# V2.net
KiCad netlist of a schematic drawn in Altium Designer
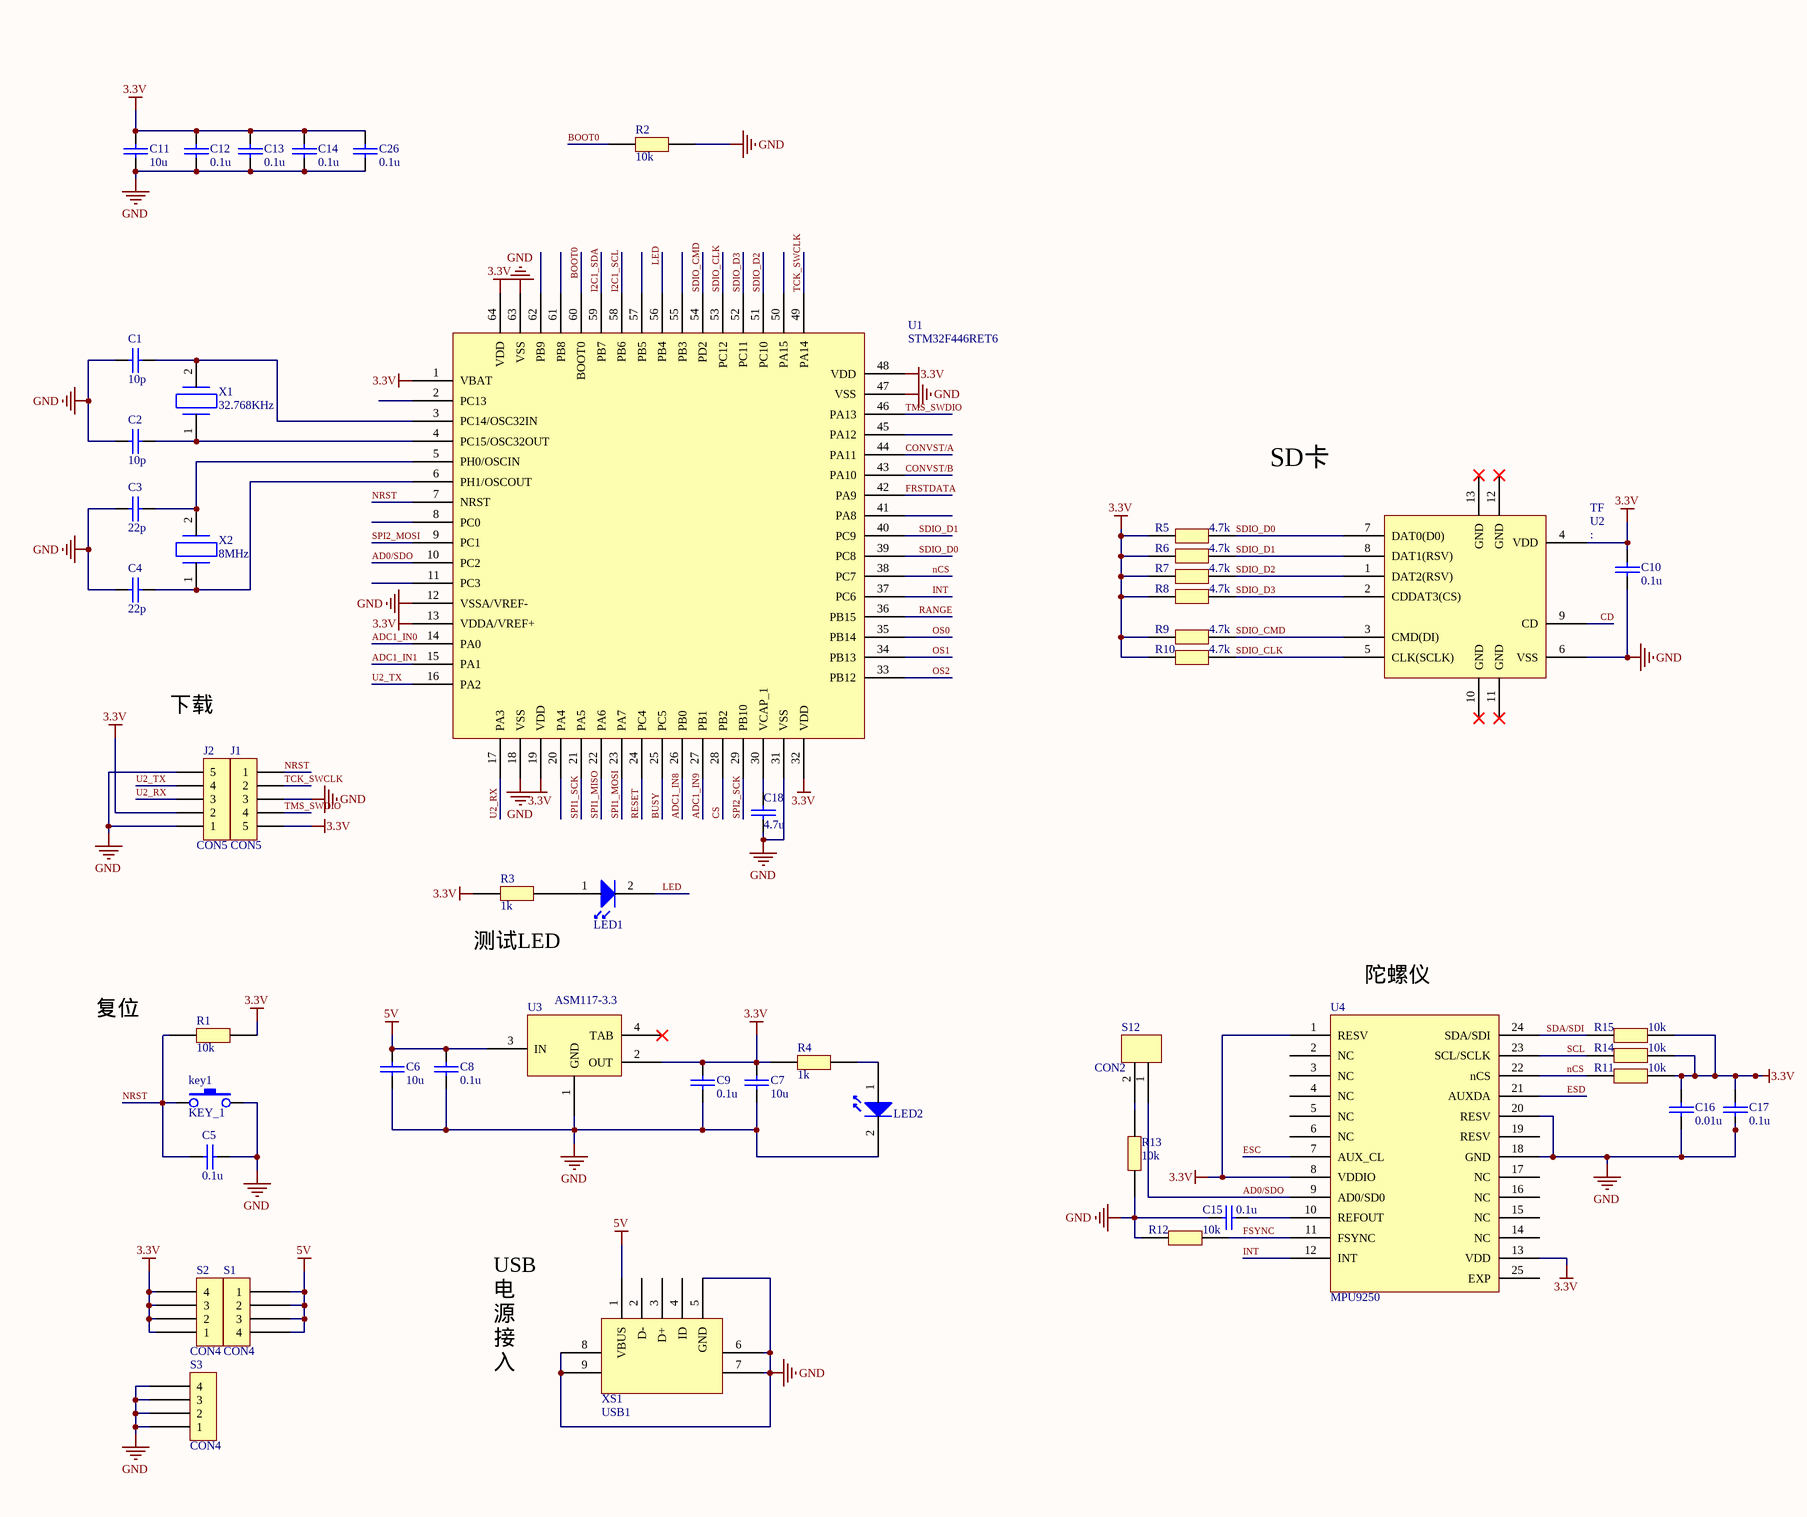
[diagram p0: V2.SchDoc, left]
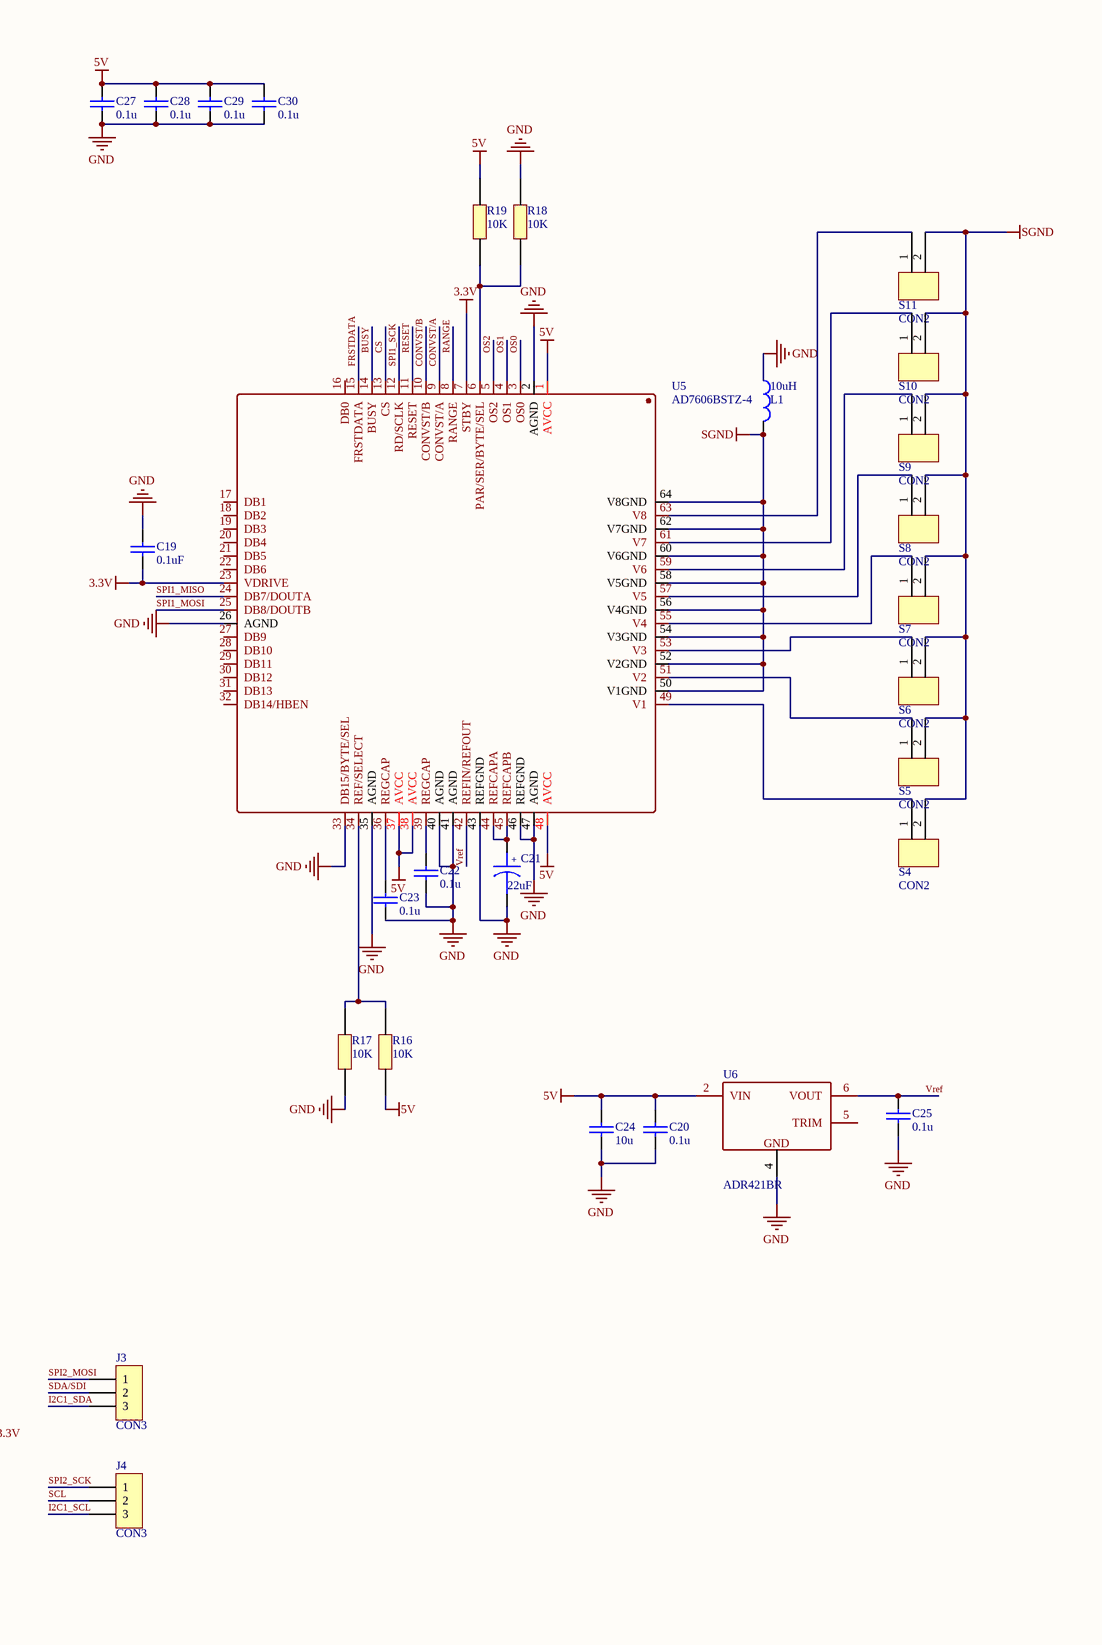
[diagram p1: V2.SchDoc, right]

(export (version "E")
  (design (tool "Eeschema 10.0.6"))
  (components
    (comp (ref "10uH") (value "L1") (footprint "0805") (libsource (lib "元件库") (part "L")))
    (comp (ref "C1") (value "10p") (footprint "0603-cap") (libsource (lib "元件库") (part "CAP")))
    (comp (ref "C2") (value "10p") (footprint "0603-cap") (libsource (lib "元件库") (part "CAP")))
    (comp (ref "C3") (value "22p") (footprint "0603-cap") (libsource (lib "元件库") (part "CAP")))
    (comp (ref "C4") (value "22p") (footprint "0603-cap") (libsource (lib "元件库") (part "CAP")))
    (comp (ref "C5") (value "0.1u") (footprint "0603-cap") (libsource (lib "元件库") (part "CAP")))
    (comp (ref "C6") (value "10u") (footprint "0603-cap") (libsource (lib "元件库") (part "CAP")))
    (comp (ref "C7") (value "10u") (footprint "0603-cap") (libsource (lib "元件库") (part "CAP")))
    (comp (ref "C8") (value "0.1u") (footprint "0603-cap") (libsource (lib "元件库") (part "CAP")))
    (comp (ref "C9") (value "0.1u") (footprint "0603-cap") (libsource (lib "元件库") (part "CAP")))
    (comp (ref "C10") (value "0.1u") (footprint "0603-cap") (libsource (lib "元件库") (part "CAP")))
    (comp (ref "C11") (value "10u") (footprint "0603-cap") (libsource (lib "元件库") (part "CAP")))
    (comp (ref "C12") (value "0.1u") (footprint "0603-cap") (libsource (lib "元件库") (part "CAP")))
    (comp (ref "C13") (value "0.1u") (footprint "0603-cap") (libsource (lib "元件库") (part "CAP")))
    (comp (ref "C14") (value "0.1u") (footprint "0603-cap") (libsource (lib "元件库") (part "CAP")))
    (comp (ref "C15") (value "0.1u") (footprint "0603-cap") (libsource (lib "元件库") (part "CAP")))
    (comp (ref "C16") (value "0.01u") (footprint "0603-cap") (libsource (lib "元件库") (part "CAP")))
    (comp (ref "C17") (value "0.1u") (footprint "0603-cap") (libsource (lib "元件库") (part "CAP")))
    (comp (ref "C18") (value "4.7u") (footprint "0603-cap") (libsource (lib "元件库") (part "CAP")))
    (comp (ref "C19") (value "0.1uF") (footprint "0603-cap") (libsource (lib "元件库") (part "CAP")))
    (comp (ref "C20") (value "0.1u") (footprint "0603-cap") (libsource (lib "元件库") (part "CAP")))
    (comp (ref "C21")
      (value "22uF")
      (footprint "C1206_Y")
      (description "Capacitor")
      (libsource (lib "元件库") (part "电解电容"))
    )
    (comp (ref "C22") (value "0.1u") (footprint "0603-cap") (libsource (lib "元件库") (part "CAP")))
    (comp (ref "C23") (value "0.1u") (footprint "0603-cap") (libsource (lib "元件库") (part "CAP")))
    (comp (ref "C24") (value "10u") (footprint "0603-cap") (libsource (lib "元件库") (part "CAP")))
    (comp (ref "C25") (value "0.1u") (footprint "0603-cap") (libsource (lib "元件库") (part "CAP")))
    (comp (ref "C26") (value "0.1u") (footprint "0603-cap") (libsource (lib "元件库") (part "CAP")))
    (comp (ref "C27") (value "0.1u") (footprint "0603-cap") (libsource (lib "元件库") (part "CAP")))
    (comp (ref "C28") (value "0.1u") (footprint "0603-cap") (libsource (lib "元件库") (part "CAP")))
    (comp (ref "C29") (value "0.1u") (footprint "0603-cap") (libsource (lib "元件库") (part "CAP")))
    (comp (ref "C30") (value "0.1u") (footprint "0603-cap") (libsource (lib "元件库") (part "CAP")))
    (comp (ref "J1") (value "CON5") (footprint "SIP05") (libsource (lib "元件库") (part "CON5")))
    (comp (ref "J2") (value "CON5") (footprint "SIP05") (libsource (lib "") (part "CON5_1")))
    (comp (ref "J3") (value "CON3") (footprint "SIP03") (libsource (lib "元件库") (part "CON3")))
    (comp (ref "J4") (value "CON3") (footprint "SIP03") (libsource (lib "元件库") (part "CON3")))
    (comp (ref "key1") (value "KEY_1") (footprint "key - duplicate5") (libsource (lib "元件库") (part "KEY_1")))
    (comp (ref "LED1") (value "LED?") (footprint "LED") (libsource (lib "元件库") (part "LED")))
    (comp (ref "LED2") (value "LED?") (footprint "LED") (libsource (lib "元件库") (part "LED")))
    (comp (ref "R1") (value "10k") (footprint "0603-res") (libsource (lib "") (part "RES_2")))
    (comp (ref "R2") (value "10k") (footprint "0603-res") (libsource (lib "") (part "RES_2")))
    (comp (ref "R3") (value "1k") (footprint "0603-res") (libsource (lib "") (part "RES_2")))
    (comp (ref "R4") (value "1k") (footprint "0603-res") (libsource (lib "") (part "RES_1")))
    (comp (ref "R5") (value "4.7k") (footprint "0603-res") (libsource (lib "") (part "RES_1")))
    (comp (ref "R6") (value "4.7k") (footprint "0603-res") (libsource (lib "") (part "RES_1")))
    (comp (ref "R7") (value "4.7k") (footprint "0603-res") (libsource (lib "") (part "RES_1")))
    (comp (ref "R8") (value "4.7k") (footprint "0603-res") (libsource (lib "") (part "RES_1")))
    (comp (ref "R9") (value "4.7k") (footprint "0603-res") (libsource (lib "") (part "RES_1")))
    (comp (ref "R10") (value "4.7k") (footprint "0603-res") (libsource (lib "") (part "RES_1")))
    (comp (ref "R11") (value "10k") (footprint "0603-res") (libsource (lib "") (part "RES_1")))
    (comp (ref "R12") (value "10k") (footprint "0603-res") (libsource (lib "") (part "RES_1")))
    (comp (ref "R13") (value "10k") (footprint "0603-res") (libsource (lib "元件库") (part "RES")))
    (comp (ref "R14") (value "10k") (footprint "0603-res") (libsource (lib "") (part "RES_1")))
    (comp (ref "R15") (value "10k") (footprint "0603-res") (libsource (lib "") (part "RES_1")))
    (comp (ref "R16") (value "10K") (footprint "0603-res") (libsource (lib "元件库") (part "RES")))
    (comp (ref "R17") (value "10K") (footprint "0603-res") (libsource (lib "元件库") (part "RES")))
    (comp (ref "R18") (value "10K") (footprint "0603-res") (libsource (lib "元件库") (part "RES")))
    (comp (ref "R19") (value "10K") (footprint "0603-res") (libsource (lib "元件库") (part "RES")))
    (comp (ref "S1") (value "CON4") (footprint "SIP04") (libsource (lib "元件库") (part "CON4")))
    (comp (ref "S2") (value "CON4") (footprint "SIP04") (libsource (lib "") (part "CON4_1")))
    (comp (ref "S3") (value "CON4") (footprint "SIP04") (libsource (lib "") (part "CON4_1")))
    (comp (ref "S4") (value "CON2") (footprint "SIP02") (libsource (lib "") (part "CON2_1")))
    (comp (ref "S5") (value "CON2") (footprint "SIP02") (libsource (lib "") (part "CON2_1")))
    (comp (ref "S6") (value "CON2") (footprint "SIP02") (libsource (lib "") (part "CON2_1")))
    (comp (ref "S7") (value "CON2") (footprint "SIP02") (libsource (lib "") (part "CON2_1")))
    (comp (ref "S8") (value "CON2") (footprint "SIP02") (libsource (lib "") (part "CON2_1")))
    (comp (ref "S9") (value "CON2") (footprint "SIP02") (libsource (lib "") (part "CON2_1")))
    (comp (ref "S10") (value "CON2") (footprint "SIP02") (libsource (lib "") (part "CON2_1")))
    (comp (ref "S11") (value "CON2") (footprint "SIP02") (libsource (lib "") (part "CON2_1")))
    (comp (ref "S12") (value "CON2") (footprint "SIP02") (libsource (lib "元件库") (part "CON2")))
    (comp (ref "TF") (value "U2") (footprint "TF-01A") (libsource (lib "元件库") (part "TF-01A")))
    (comp (ref "U1")
      (value "STM32F446RET6")
      (footprint "LQFP-64_10X10X05P")
      (libsource (lib "元件库") (part "STM32F446RET6"))
    )
    (comp (ref "U3") (value "ASM117-3.3") (footprint "SOT-223") (libsource (lib "元件库") (part "ASM117-3.3")))
    (comp (ref "U4")
      (value "MPU9250")
      (footprint "QFN-24-1EP_3X3MM_PITCH0.4MM")
      (libsource (lib "元件库") (part "MPU9250"))
    )
    (comp (ref "U5")
      (value "AD7606BSTZ-4")
      (footprint "AD7606")
      (libsource (lib "元件库") (part "AD7606BSTZ-4"))
    )
    (comp (ref "U6") (value "ADR421BR") (footprint "ADR421") (libsource (lib "元件库") (part "ADR421")))
    (comp (ref "X1") (value "32.768KHz") (footprint "XTAL-B") (libsource (lib "元件库") (part "XTAL")))
    (comp (ref "X2") (value "8MHz") (footprint "XTAL2") (libsource (lib "元件库") (part "XTAL")))
    (comp (ref "XS1") (value "USB1") (footprint "micro USB") (libsource (lib "元件库") (part "USB1")))
  )
  (nets
    (net (code "1") (name "/AD0{slash}SDO") (class "Default")
      (node (ref "S12") (pin "1") (pinfunction "1_1") (pintype "passive"))
      (node (ref "U1") (pin "10") (pinfunction "PC2_10") (pintype "passive"))
      (node (ref "U4") (pin "9") (pinfunction "AD0/SD0_9") (pintype "passive"))
    )
    (net (code "2") (name "/ADC1_IN0") (class "Default")
      (node (ref "U1") (pin "14") (pinfunction "PA0_14") (pintype "passive"))
    )
    (net (code "3") (name "/ADC1_IN1") (class "Default")
      (node (ref "U1") (pin "15") (pinfunction "PA1_15") (pintype "passive"))
    )
    (net (code "4") (name "/ADC1_IN8") (class "Default")
      (node (ref "U1") (pin "26") (pinfunction "PB0_26") (pintype "passive"))
    )
    (net (code "5") (name "/ADC1_IN9") (class "Default")
      (node (ref "U1") (pin "27") (pinfunction "PB1_27") (pintype "passive"))
    )
    (net (code "6") (name "/BOOT0") (class "Default")
      (node (ref "R2") (pin "2") (pinfunction "2_2") (pintype "passive"))
      (node (ref "U1") (pin "60") (pinfunction "BOOT0_60") (pintype "passive"))
    )
    (net (code "7") (name "/BUSY") (class "Default")
      (node (ref "U1") (pin "25") (pinfunction "PC5_25") (pintype "passive"))
      (node (ref "U5") (pin "14") (pinfunction "BUSY_14") (pintype "passive"))
    )
    (net (code "8") (name "/CD") (class "Default")
      (node (ref "TF") (pin "9") (pinfunction "CD_9") (pintype "passive"))
    )
    (net (code "9") (name "/CONVST{slash}A") (class "Default")
      (node (ref "U1") (pin "44") (pinfunction "PA11_44") (pintype "passive"))
      (node (ref "U5") (pin "9") (pinfunction "CONVST/A_9") (pintype "passive"))
    )
    (net (code "10") (name "/CONVST{slash}B") (class "Default")
      (node (ref "U1") (pin "43") (pinfunction "PA10_43") (pintype "passive"))
      (node (ref "U5") (pin "10") (pinfunction "CONVST/B_10") (pintype "passive"))
    )
    (net (code "11") (name "/CS") (class "Default")
      (node (ref "U1") (pin "28") (pinfunction "PB2_28") (pintype "passive"))
      (node (ref "U5") (pin "13") (pinfunction "CS_13") (pintype "passive"))
    )
    (net (code "12") (name "/ESC") (class "Default")
      (node (ref "U4") (pin "7") (pinfunction "AUX_CL_7") (pintype "passive"))
    )
    (net (code "13") (name "/ESD") (class "Default")
      (node (ref "U4") (pin "21") (pinfunction "AUXDA_21") (pintype "passive"))
    )
    (net (code "14") (name "/FRSTDATA") (class "Default")
      (node (ref "U1") (pin "42") (pinfunction "PA9_42") (pintype "passive"))
      (node (ref "U5") (pin "15") (pinfunction "FRSTDATA_15") (pintype "passive"))
    )
    (net (code "15") (name "/FSYNC") (class "Default")
      (node (ref "R12") (pin "2") (pinfunction "2_2") (pintype "passive"))
      (node (ref "U4") (pin "11") (pinfunction "FSYNC_11") (pintype "passive"))
    )
    (net (code "16") (name "/I2C1_SCL") (class "Default")
      (node (ref "J4") (pin "3") (pinfunction "3_3") (pintype "passive"))
      (node (ref "U1") (pin "58") (pinfunction "PB6_58") (pintype "passive"))
    )
    (net (code "17") (name "/I2C1_SDA") (class "Default")
      (node (ref "J3") (pin "3") (pinfunction "3_3") (pintype "passive"))
      (node (ref "U1") (pin "59") (pinfunction "PB7_59") (pintype "passive"))
    )
    (net (code "18") (name "/INT") (class "Default")
      (node (ref "U1") (pin "37") (pinfunction "PC6_37") (pintype "passive"))
      (node (ref "U4") (pin "12") (pinfunction "INT_12") (pintype "passive"))
    )
    (net (code "19") (name "/LED") (class "Default")
      (node (ref "LED1") (pin "2") (pinfunction "2_2") (pintype "passive"))
      (node (ref "U1") (pin "56") (pinfunction "PB4_56") (pintype "passive"))
    )
    (net (code "20") (name "/NRST") (class "Default")
      (node (ref "C5") (pin "1") (pinfunction "1_1") (pintype "passive"))
      (node (ref "J1") (pin "1") (pinfunction "1_1") (pintype "passive"))
      (node (ref "R1") (pin "2") (pinfunction "2_2") (pintype "passive"))
      (node (ref "U1") (pin "7") (pinfunction "NRST_7") (pintype "passive"))
      (node (ref "key1") (pin "1") (pinfunction "1_1") (pintype "passive"))
    )
    (net (code "21") (name "/OS0") (class "Default")
      (node (ref "U1") (pin "35") (pinfunction "PB14_35") (pintype "passive"))
      (node (ref "U5") (pin "3") (pinfunction "OS0_3") (pintype "passive"))
    )
    (net (code "22") (name "/OS1") (class "Default")
      (node (ref "U1") (pin "34") (pinfunction "PB13_34") (pintype "passive"))
      (node (ref "U5") (pin "4") (pinfunction "OS1_4") (pintype "passive"))
    )
    (net (code "23") (name "/OS2") (class "Default")
      (node (ref "U1") (pin "33") (pinfunction "PB12_33") (pintype "passive"))
      (node (ref "U5") (pin "5") (pinfunction "OS2_5") (pintype "passive"))
    )
    (net (code "24") (name "/RANGE") (class "Default")
      (node (ref "U1") (pin "36") (pinfunction "PB15_36") (pintype "passive"))
      (node (ref "U5") (pin "8") (pinfunction "RANGE_8") (pintype "passive"))
    )
    (net (code "25") (name "/RESET") (class "Default")
      (node (ref "U1") (pin "24") (pinfunction "PC4_24") (pintype "passive"))
      (node (ref "U5") (pin "11") (pinfunction "RESET_11") (pintype "passive"))
    )
    (net (code "26") (name "/SCL") (class "Default")
      (node (ref "J4") (pin "2") (pinfunction "2_2") (pintype "passive"))
      (node (ref "R14") (pin "1") (pinfunction "1_1") (pintype "passive"))
      (node (ref "U4") (pin "23") (pinfunction "SCL/SCLK_23") (pintype "passive"))
    )
    (net (code "27") (name "/SDA{slash}SDI") (class "Default")
      (node (ref "J3") (pin "2") (pinfunction "2_2") (pintype "passive"))
      (node (ref "R15") (pin "1") (pinfunction "1_1") (pintype "passive"))
      (node (ref "U4") (pin "24") (pinfunction "SDA/SDI_24") (pintype "passive"))
    )
    (net (code "28") (name "/SDIO_CLK") (class "Default")
      (node (ref "R10") (pin "2") (pinfunction "2_2") (pintype "passive"))
      (node (ref "TF") (pin "5") (pinfunction "CLK(SCLK)_5") (pintype "passive"))
      (node (ref "U1") (pin "53") (pinfunction "PC12_53") (pintype "passive"))
    )
    (net (code "29") (name "/SDIO_CMD") (class "Default")
      (node (ref "R9") (pin "2") (pinfunction "2_2") (pintype "passive"))
      (node (ref "TF") (pin "3") (pinfunction "CMD(DI)_3") (pintype "passive"))
      (node (ref "U1") (pin "54") (pinfunction "PD2_54") (pintype "passive"))
    )
    (net (code "30") (name "/SDIO_D0") (class "Default")
      (node (ref "R5") (pin "2") (pinfunction "2_2") (pintype "passive"))
      (node (ref "TF") (pin "7") (pinfunction "DAT0(D0)_7") (pintype "passive"))
      (node (ref "U1") (pin "39") (pinfunction "PC8_39") (pintype "passive"))
    )
    (net (code "31") (name "/SDIO_D1") (class "Default")
      (node (ref "R6") (pin "2") (pinfunction "2_2") (pintype "passive"))
      (node (ref "TF") (pin "8") (pinfunction "DAT1(RSV)_8") (pintype "passive"))
      (node (ref "U1") (pin "40") (pinfunction "PC9_40") (pintype "passive"))
    )
    (net (code "32") (name "/SDIO_D2") (class "Default")
      (node (ref "R7") (pin "2") (pinfunction "2_2") (pintype "passive"))
      (node (ref "TF") (pin "1") (pinfunction "DAT2(RSV)_1") (pintype "passive"))
      (node (ref "U1") (pin "51") (pinfunction "PC10_51") (pintype "passive"))
    )
    (net (code "33") (name "/SDIO_D3") (class "Default")
      (node (ref "R8") (pin "2") (pinfunction "2_2") (pintype "passive"))
      (node (ref "TF") (pin "2") (pinfunction "CDDAT3(CS)_2") (pintype "passive"))
      (node (ref "U1") (pin "52") (pinfunction "PC11_52") (pintype "passive"))
    )
    (net (code "34") (name "/SPI1_MISO") (class "Default")
      (node (ref "U1") (pin "22") (pinfunction "PA6_22") (pintype "passive"))
      (node (ref "U5") (pin "24") (pinfunction "DB7/DOUTA_24") (pintype "passive"))
    )
    (net (code "35") (name "/SPI1_MOSI") (class "Default")
      (node (ref "U1") (pin "23") (pinfunction "PA7_23") (pintype "passive"))
      (node (ref "U5") (pin "25") (pinfunction "DB8/DOUTB_25") (pintype "passive"))
    )
    (net (code "36") (name "/SPI1_SCK") (class "Default")
      (node (ref "U1") (pin "21") (pinfunction "PA5_21") (pintype "passive"))
      (node (ref "U5") (pin "12") (pinfunction "RD/SCLK_12") (pintype "passive"))
    )
    (net (code "37") (name "/SPI2_MOSI") (class "Default")
      (node (ref "J3") (pin "1") (pinfunction "1_1") (pintype "passive"))
      (node (ref "U1") (pin "9") (pinfunction "PC1_9") (pintype "passive"))
    )
    (net (code "38") (name "/SPI2_SCK") (class "Default")
      (node (ref "J4") (pin "1") (pinfunction "1_1") (pintype "passive"))
      (node (ref "U1") (pin "29") (pinfunction "PB10_29") (pintype "passive"))
    )
    (net (code "39") (name "/TCK_SWCLK") (class "Default")
      (node (ref "J1") (pin "2") (pinfunction "2_2") (pintype "passive"))
      (node (ref "U1") (pin "49") (pinfunction "PA14_49") (pintype "passive"))
    )
    (net (code "40") (name "/TMS_SWDIO") (class "Default")
      (node (ref "J1") (pin "4") (pinfunction "4_4") (pintype "passive"))
      (node (ref "U1") (pin "46") (pinfunction "PA13_46") (pintype "passive"))
    )
    (net (code "41") (name "/U2_RX") (class "Default")
      (node (ref "J2") (pin "3") (pinfunction "3_3") (pintype "passive"))
      (node (ref "U1") (pin "17") (pinfunction "PA3_17") (pintype "passive"))
    )
    (net (code "42") (name "/U2_TX") (class "Default")
      (node (ref "J2") (pin "4") (pinfunction "4_4") (pintype "passive"))
      (node (ref "U1") (pin "16") (pinfunction "PA2_16") (pintype "passive"))
    )
    (net (code "43") (name "/Vref") (class "Default")
      (node (ref "C25") (pin "1") (pinfunction "1_1") (pintype "passive"))
      (node (ref "U5") (pin "42") (pinfunction "REFIN/REFOUT_42") (pintype "passive"))
      (node (ref "U6") (pin "6") (pinfunction "VOUT_6") (pintype "passive"))
    )
    (net (code "44") (name "/nCS") (class "Default")
      (node (ref "R11") (pin "1") (pinfunction "1_1") (pintype "passive"))
      (node (ref "U1") (pin "38") (pinfunction "PC7_38") (pintype "passive"))
      (node (ref "U4") (pin "22") (pinfunction "nCS_22") (pintype "passive"))
    )
    (net (code "45") (name "3.3V") (class "Default")
      (node (ref "C10") (pin "1") (pinfunction "1_1") (pintype "passive"))
      (node (ref "C11") (pin "1") (pinfunction "1_1") (pintype "passive"))
      (node (ref "C12") (pin "1") (pinfunction "1_1") (pintype "passive"))
      (node (ref "C13") (pin "1") (pinfunction "1_1") (pintype "passive"))
      (node (ref "C14") (pin "1") (pinfunction "1_1") (pintype "passive"))
      (node (ref "C16") (pin "2") (pinfunction "2_2") (pintype "passive"))
      (node (ref "C17") (pin "2") (pinfunction "2_2") (pintype "passive"))
      (node (ref "C19") (pin "1") (pinfunction "1_1") (pintype "passive"))
      (node (ref "C26") (pin "1") (pinfunction "1_1") (pintype "passive"))
      (node (ref "C7") (pin "1") (pinfunction "1_1") (pintype "passive"))
      (node (ref "C9") (pin "1") (pinfunction "1_1") (pintype "passive"))
      (node (ref "J1") (pin "5") (pinfunction "5_5") (pintype "passive"))
      (node (ref "J2") (pin "2") (pinfunction "2_2") (pintype "passive"))
      (node (ref "R1") (pin "1") (pinfunction "1_1") (pintype "passive"))
      (node (ref "R10") (pin "1") (pinfunction "1_1") (pintype "passive"))
      (node (ref "R11") (pin "2") (pinfunction "2_2") (pintype "passive"))
      (node (ref "R14") (pin "2") (pinfunction "2_2") (pintype "passive"))
      (node (ref "R15") (pin "2") (pinfunction "2_2") (pintype "passive"))
      (node (ref "R3") (pin "2") (pinfunction "2_2") (pintype "passive"))
      (node (ref "R4") (pin "1") (pinfunction "1_1") (pintype "passive"))
      (node (ref "R5") (pin "1") (pinfunction "1_1") (pintype "passive"))
      (node (ref "R6") (pin "1") (pinfunction "1_1") (pintype "passive"))
      (node (ref "R7") (pin "1") (pinfunction "1_1") (pintype "passive"))
      (node (ref "R8") (pin "1") (pinfunction "1_1") (pintype "passive"))
      (node (ref "R9") (pin "1") (pinfunction "1_1") (pintype "passive"))
      (node (ref "S2") (pin "1") (pinfunction "1_1") (pintype "passive"))
      (node (ref "S2") (pin "2") (pinfunction "2_2") (pintype "passive"))
      (node (ref "S2") (pin "3") (pinfunction "3_3") (pintype "passive"))
      (node (ref "S2") (pin "4") (pinfunction "4_4") (pintype "passive"))
      (node (ref "TF") (pin "4") (pinfunction "VDD_4") (pintype "passive"))
      (node (ref "U1") (pin "1") (pinfunction "VBAT_1") (pintype "passive"))
      (node (ref "U1") (pin "13") (pinfunction "VDDA/VREF+_13") (pintype "passive"))
      (node (ref "U1") (pin "19") (pinfunction "VDD_19") (pintype "passive"))
      (node (ref "U1") (pin "32") (pinfunction "VDD_32") (pintype "passive"))
      (node (ref "U1") (pin "48") (pinfunction "VDD_48") (pintype "passive"))
      (node (ref "U1") (pin "64") (pinfunction "VDD_64") (pintype "passive"))
      (node (ref "U3") (pin "2") (pinfunction "OUT_2") (pintype "passive"))
      (node (ref "U4") (pin "1") (pinfunction "RESV_1") (pintype "passive"))
      (node (ref "U4") (pin "13") (pinfunction "VDD_13") (pintype "passive"))
      (node (ref "U4") (pin "8") (pinfunction "VDDIO_8") (pintype "passive"))
      (node (ref "U5") (pin "23") (pinfunction "VDRIVE_23") (pintype "passive"))
      (node (ref "U5") (pin "7") (pinfunction "STBY_7") (pintype "passive"))
    )
    (net (code "46") (name "5V") (class "Default")
      (node (ref "C20") (pin "2") (pinfunction "2_2") (pintype "passive"))
      (node (ref "C24") (pin "1") (pinfunction "1_1") (pintype "passive"))
      (node (ref "C27") (pin "1") (pinfunction "1_1") (pintype "passive"))
      (node (ref "C28") (pin "1") (pinfunction "1_1") (pintype "passive"))
      (node (ref "C29") (pin "1") (pinfunction "1_1") (pintype "passive"))
      (node (ref "C30") (pin "1") (pinfunction "1_1") (pintype "passive"))
      (node (ref "C6") (pin "1") (pinfunction "1_1") (pintype "passive"))
      (node (ref "C8") (pin "1") (pinfunction "1_1") (pintype "passive"))
      (node (ref "R16") (pin "1") (pinfunction "1_1") (pintype "passive"))
      (node (ref "R19") (pin "2") (pinfunction "2_2") (pintype "passive"))
      (node (ref "S1") (pin "1") (pinfunction "1_1") (pintype "passive"))
      (node (ref "S1") (pin "2") (pinfunction "2_2") (pintype "passive"))
      (node (ref "S1") (pin "3") (pinfunction "3_3") (pintype "passive"))
      (node (ref "S1") (pin "4") (pinfunction "4_4") (pintype "passive"))
      (node (ref "U3") (pin "3") (pinfunction "IN_3") (pintype "passive"))
      (node (ref "U5") (pin "1") (pinfunction "AVCC_1") (pintype "passive"))
      (node (ref "U5") (pin "37") (pinfunction "AVCC_37") (pintype "passive"))
      (node (ref "U5") (pin "38") (pinfunction "AVCC_38") (pintype "passive"))
      (node (ref "U5") (pin "48") (pinfunction "AVCC_48") (pintype "passive"))
      (node (ref "U6") (pin "2") (pinfunction "VIN_2") (pintype "passive"))
      (node (ref "XS1") (pin "1") (pinfunction "VBUS_1") (pintype "passive"))
    )
    (net (code "47") (name "GND") (class "Default")
      (node (ref "10uH") (pin "2") (pinfunction "2_2") (pintype "passive"))
      (node (ref "C1") (pin "1") (pinfunction "1_1") (pintype "passive"))
      (node (ref "C10") (pin "2") (pinfunction "2_2") (pintype "passive"))
      (node (ref "C11") (pin "2") (pinfunction "2_2") (pintype "passive"))
      (node (ref "C12") (pin "2") (pinfunction "2_2") (pintype "passive"))
      (node (ref "C13") (pin "2") (pinfunction "2_2") (pintype "passive"))
      (node (ref "C14") (pin "2") (pinfunction "2_2") (pintype "passive"))
      (node (ref "C15") (pin "1") (pinfunction "1_1") (pintype "passive"))
      (node (ref "C16") (pin "1") (pinfunction "1_1") (pintype "passive"))
      (node (ref "C17") (pin "1") (pinfunction "1_1") (pintype "passive"))
      (node (ref "C18") (pin "1") (pinfunction "1_1") (pintype "passive"))
      (node (ref "C19") (pin "2") (pinfunction "2_2") (pintype "passive"))
      (node (ref "C2") (pin "1") (pinfunction "1_1") (pintype "passive"))
      (node (ref "C20") (pin "1") (pinfunction "1_1") (pintype "passive"))
      (node (ref "C21") (pin "2") (pinfunction "2_2") (pintype "passive"))
      (node (ref "C22") (pin "1") (pinfunction "1_1") (pintype "passive"))
      (node (ref "C23") (pin "2") (pinfunction "2_2") (pintype "passive"))
      (node (ref "C24") (pin "2") (pinfunction "2_2") (pintype "passive"))
      (node (ref "C25") (pin "2") (pinfunction "2_2") (pintype "passive"))
      (node (ref "C26") (pin "2") (pinfunction "2_2") (pintype "passive"))
      (node (ref "C27") (pin "2") (pinfunction "2_2") (pintype "passive"))
      (node (ref "C28") (pin "2") (pinfunction "2_2") (pintype "passive"))
      (node (ref "C29") (pin "2") (pinfunction "2_2") (pintype "passive"))
      (node (ref "C3") (pin "1") (pinfunction "1_1") (pintype "passive"))
      (node (ref "C30") (pin "2") (pinfunction "2_2") (pintype "passive"))
      (node (ref "C4") (pin "1") (pinfunction "1_1") (pintype "passive"))
      (node (ref "C5") (pin "2") (pinfunction "2_2") (pintype "passive"))
      (node (ref "C6") (pin "2") (pinfunction "2_2") (pintype "passive"))
      (node (ref "C7") (pin "2") (pinfunction "2_2") (pintype "passive"))
      (node (ref "C8") (pin "2") (pinfunction "2_2") (pintype "passive"))
      (node (ref "C9") (pin "2") (pinfunction "2_2") (pintype "passive"))
      (node (ref "J1") (pin "3") (pinfunction "3_3") (pintype "passive"))
      (node (ref "J2") (pin "1") (pinfunction "1_1") (pintype "passive"))
      (node (ref "J2") (pin "5") (pinfunction "5_5") (pintype "passive"))
      (node (ref "LED2") (pin "2") (pinfunction "2_2") (pintype "passive"))
      (node (ref "R12") (pin "1") (pinfunction "1_1") (pintype "passive"))
      (node (ref "R13") (pin "1") (pinfunction "1_1") (pintype "passive"))
      (node (ref "R17") (pin "1") (pinfunction "1_1") (pintype "passive"))
      (node (ref "R18") (pin "2") (pinfunction "2_2") (pintype "passive"))
      (node (ref "R2") (pin "1") (pinfunction "1_1") (pintype "passive"))
      (node (ref "S3") (pin "1") (pinfunction "1_1") (pintype "passive"))
      (node (ref "S3") (pin "2") (pinfunction "2_2") (pintype "passive"))
      (node (ref "S3") (pin "3") (pinfunction "3_3") (pintype "passive"))
      (node (ref "S3") (pin "4") (pinfunction "4_4") (pintype "passive"))
      (node (ref "TF") (pin "6") (pinfunction "VSS_6") (pintype "passive"))
      (node (ref "U1") (pin "12") (pinfunction "VSSA/VREF-_12") (pintype "passive"))
      (node (ref "U1") (pin "18") (pinfunction "VSS_18") (pintype "passive"))
      (node (ref "U1") (pin "31") (pinfunction "VSS_31") (pintype "passive"))
      (node (ref "U1") (pin "47") (pinfunction "VSS_47") (pintype "passive"))
      (node (ref "U1") (pin "63") (pinfunction "VSS_63") (pintype "passive"))
      (node (ref "U3") (pin "1") (pinfunction "GND_1") (pintype "passive"))
      (node (ref "U4") (pin "18") (pinfunction "GND_18") (pintype "passive"))
      (node (ref "U4") (pin "20") (pinfunction "RESV_20") (pintype "passive"))
      (node (ref "U5") (pin "2") (pinfunction "AGND_2") (pintype "passive"))
      (node (ref "U5") (pin "26") (pinfunction "AGND_26") (pintype "passive"))
      (node (ref "U5") (pin "33") (pinfunction "DB15/BYTE/SEL_33") (pintype "passive"))
      (node (ref "U5") (pin "35") (pinfunction "AGND_35") (pintype "passive"))
      (node (ref "U5") (pin "40") (pinfunction "AGND_40") (pintype "passive"))
      (node (ref "U5") (pin "41") (pinfunction "AGND_41") (pintype "passive"))
      (node (ref "U5") (pin "43") (pinfunction "REFGND_43") (pintype "passive"))
      (node (ref "U5") (pin "46") (pinfunction "REFGND_46") (pintype "passive"))
      (node (ref "U5") (pin "47") (pinfunction "AGND_47") (pintype "passive"))
      (node (ref "U6") (pin "4") (pinfunction "GND_4") (pintype "passive"))
      (node (ref "XS1") (pin "5") (pinfunction "GND_5") (pintype "passive"))
      (node (ref "XS1") (pin "6") (pinfunction "6_6") (pintype "passive"))
      (node (ref "XS1") (pin "7") (pinfunction "7_7") (pintype "passive"))
      (node (ref "XS1") (pin "8") (pinfunction "8_8") (pintype "passive"))
      (node (ref "XS1") (pin "9") (pinfunction "9_9") (pintype "passive"))
      (node (ref "key1") (pin "2") (pinfunction "2_2") (pintype "passive"))
    )
    (net (code "48") (name "Net-(C22-Pad2)") (class "Default")
      (node (ref "C22") (pin "2") (pinfunction "2_2") (pintype "passive"))
      (node (ref "U5") (pin "39") (pinfunction "REGCAP_39") (pintype "passive"))
    )
    (net (code "49") (name "Net-(C23-Pad1)") (class "Default")
      (node (ref "C23") (pin "1") (pinfunction "1_1") (pintype "passive"))
      (node (ref "U5") (pin "36") (pinfunction "REGCAP_36") (pintype "passive"))
    )
    (net (code "50") (name "Net-(LED1-Pad1)") (class "Default")
      (node (ref "LED1") (pin "1") (pinfunction "1_1") (pintype "passive"))
      (node (ref "R3") (pin "1") (pinfunction "1_1") (pintype "passive"))
    )
    (net (code "51") (name "Net-(LED2-Pad1)") (class "Default")
      (node (ref "LED2") (pin "1") (pinfunction "1_1") (pintype "passive"))
      (node (ref "R4") (pin "2") (pinfunction "2_2") (pintype "passive"))
    )
    (net (code "52") (name "Net-(R13-Pad2)") (class "Default")
      (node (ref "R13") (pin "2") (pinfunction "2_2") (pintype "passive"))
      (node (ref "S12") (pin "2") (pinfunction "2_2") (pintype "passive"))
    )
    (net (code "53") (name "Net-(U1-PC14{slash}OSC32IN)") (class "Default")
      (node (ref "C1") (pin "2") (pinfunction "2_2") (pintype "passive"))
      (node (ref "U1") (pin "3") (pinfunction "PC14/OSC32IN_3") (pintype "passive"))
      (node (ref "X1") (pin "2") (pinfunction "2_2") (pintype "passive"))
    )
    (net (code "54") (name "Net-(U1-PC15{slash}OSC32OUT)") (class "Default")
      (node (ref "C2") (pin "2") (pinfunction "2_2") (pintype "passive"))
      (node (ref "U1") (pin "4") (pinfunction "PC15/OSC32OUT_4") (pintype "passive"))
      (node (ref "X1") (pin "1") (pinfunction "1_1") (pintype "passive"))
    )
    (net (code "55") (name "Net-(U1-PH0{slash}OSCIN)") (class "Default")
      (node (ref "C3") (pin "2") (pinfunction "2_2") (pintype "passive"))
      (node (ref "U1") (pin "5") (pinfunction "PH0/OSCIN_5") (pintype "passive"))
      (node (ref "X2") (pin "2") (pinfunction "2_2") (pintype "passive"))
    )
    (net (code "56") (name "Net-(U1-PH1{slash}OSCOUT)") (class "Default")
      (node (ref "C4") (pin "2") (pinfunction "2_2") (pintype "passive"))
      (node (ref "U1") (pin "6") (pinfunction "PH1/OSCOUT_6") (pintype "passive"))
      (node (ref "X2") (pin "1") (pinfunction "1_1") (pintype "passive"))
    )
    (net (code "57") (name "Net-(U1-VCAP_1)") (class "Default")
      (node (ref "C18") (pin "2") (pinfunction "2_2") (pintype "passive"))
      (node (ref "U1") (pin "30") (pinfunction "VCAP_1_30") (pintype "passive"))
    )
    (net (code "58") (name "Net-(U4-REFOUT)") (class "Default")
      (node (ref "C15") (pin "2") (pinfunction "2_2") (pintype "passive"))
      (node (ref "U4") (pin "10") (pinfunction "REFOUT_10") (pintype "passive"))
    )
    (net (code "59") (name "Net-(U5-PAR{slash}SER{slash}BYTE{slash}SEL)") (class "Default")
      (node (ref "R18") (pin "1") (pinfunction "1_1") (pintype "passive"))
      (node (ref "R19") (pin "1") (pinfunction "1_1") (pintype "passive"))
      (node (ref "U5") (pin "6") (pinfunction "PAR/SER/BYTE/SEL_6") (pintype "passive"))
    )
    (net (code "60") (name "Net-(U5-REFCAPA)") (class "Default")
      (node (ref "C21") (pin "1") (pinfunction "1_1") (pintype "passive"))
      (node (ref "U5") (pin "44") (pinfunction "REFCAPA_44") (pintype "passive"))
      (node (ref "U5") (pin "45") (pinfunction "REFCAPB_45") (pintype "passive"))
    )
    (net (code "61") (name "Net-(U5-REF{slash}SELECT)") (class "Default")
      (node (ref "R16") (pin "2") (pinfunction "2_2") (pintype "passive"))
      (node (ref "R17") (pin "2") (pinfunction "2_2") (pintype "passive"))
      (node (ref "U5") (pin "34") (pinfunction "REF/SELECT_34") (pintype "passive"))
    )
    (net (code "62") (name "Net-(U5-V1)") (class "Default")
      (node (ref "S4") (pin "1") (pinfunction "1_1") (pintype "passive"))
      (node (ref "U5") (pin "49") (pinfunction "V1_49") (pintype "passive"))
    )
    (net (code "63") (name "Net-(U5-V2)") (class "Default")
      (node (ref "S5") (pin "1") (pinfunction "1_1") (pintype "passive"))
      (node (ref "U5") (pin "51") (pinfunction "V2_51") (pintype "passive"))
    )
    (net (code "64") (name "Net-(U5-V3)") (class "Default")
      (node (ref "S6") (pin "1") (pinfunction "1_1") (pintype "passive"))
      (node (ref "U5") (pin "53") (pinfunction "V3_53") (pintype "passive"))
    )
    (net (code "65") (name "Net-(U5-V4)") (class "Default")
      (node (ref "S7") (pin "1") (pinfunction "1_1") (pintype "passive"))
      (node (ref "U5") (pin "55") (pinfunction "V4_55") (pintype "passive"))
    )
    (net (code "66") (name "Net-(U5-V5)") (class "Default")
      (node (ref "S8") (pin "1") (pinfunction "1_1") (pintype "passive"))
      (node (ref "U5") (pin "57") (pinfunction "V5_57") (pintype "passive"))
    )
    (net (code "67") (name "Net-(U5-V6)") (class "Default")
      (node (ref "S9") (pin "1") (pinfunction "1_1") (pintype "passive"))
      (node (ref "U5") (pin "59") (pinfunction "V6_59") (pintype "passive"))
    )
    (net (code "68") (name "Net-(U5-V7)") (class "Default")
      (node (ref "S10") (pin "1") (pinfunction "1_1") (pintype "passive"))
      (node (ref "U5") (pin "61") (pinfunction "V7_61") (pintype "passive"))
    )
    (net (code "69") (name "Net-(U5-V8)") (class "Default")
      (node (ref "S11") (pin "1") (pinfunction "1_1") (pintype "passive"))
      (node (ref "U5") (pin "63") (pinfunction "V8_63") (pintype "passive"))
    )
    (net (code "70") (name "SGND") (class "Default")
      (node (ref "10uH") (pin "1") (pinfunction "1_1") (pintype "passive"))
      (node (ref "S10") (pin "2") (pinfunction "2_2") (pintype "passive"))
      (node (ref "S11") (pin "2") (pinfunction "2_2") (pintype "passive"))
      (node (ref "S4") (pin "2") (pinfunction "2_2") (pintype "passive"))
      (node (ref "S5") (pin "2") (pinfunction "2_2") (pintype "passive"))
      (node (ref "S6") (pin "2") (pinfunction "2_2") (pintype "passive"))
      (node (ref "S7") (pin "2") (pinfunction "2_2") (pintype "passive"))
      (node (ref "S8") (pin "2") (pinfunction "2_2") (pintype "passive"))
      (node (ref "S9") (pin "2") (pinfunction "2_2") (pintype "passive"))
      (node (ref "U5") (pin "50") (pinfunction "V1GND_50") (pintype "passive"))
      (node (ref "U5") (pin "52") (pinfunction "V2GND_52") (pintype "passive"))
      (node (ref "U5") (pin "54") (pinfunction "V3GND_54") (pintype "passive"))
      (node (ref "U5") (pin "56") (pinfunction "V4GND_56") (pintype "passive"))
      (node (ref "U5") (pin "58") (pinfunction "V5GND_58") (pintype "passive"))
      (node (ref "U5") (pin "60") (pinfunction "V6GND_60") (pintype "passive"))
      (node (ref "U5") (pin "62") (pinfunction "V7GND_62") (pintype "passive"))
      (node (ref "U5") (pin "64") (pinfunction "V8GND_64") (pintype "passive"))
    )
    (net (code "71") (name "unconnected-(TF-GND-Pad10)") (class "Default")
      (node (ref "TF") (pin "10") (pinfunction "GND_10") (pintype "passive+no_connect"))
    )
    (net (code "72") (name "unconnected-(TF-GND-Pad11)") (class "Default")
      (node (ref "TF") (pin "11") (pinfunction "GND_11") (pintype "passive+no_connect"))
    )
    (net (code "73") (name "unconnected-(TF-GND-Pad12)") (class "Default")
      (node (ref "TF") (pin "12") (pinfunction "GND_12") (pintype "passive+no_connect"))
    )
    (net (code "74") (name "unconnected-(TF-GND-Pad13)") (class "Default")
      (node (ref "TF") (pin "13") (pinfunction "GND_13") (pintype "passive+no_connect"))
    )
    (net (code "75") (name "unconnected-(U1-PA4-Pad20)") (class "Default")
      (node (ref "U1") (pin "20") (pinfunction "PA4_20") (pintype "passive"))
    )
    (net (code "76") (name "unconnected-(U1-PA8-Pad41)") (class "Default")
      (node (ref "U1") (pin "41") (pinfunction "PA8_41") (pintype "passive"))
    )
    (net (code "77") (name "unconnected-(U1-PA12-Pad45)") (class "Default")
      (node (ref "U1") (pin "45") (pinfunction "PA12_45") (pintype "passive"))
    )
    (net (code "78") (name "unconnected-(U1-PA15-Pad50)") (class "Default")
      (node (ref "U1") (pin "50") (pinfunction "PA15_50") (pintype "passive"))
    )
    (net (code "79") (name "unconnected-(U1-PB3-Pad55)") (class "Default")
      (node (ref "U1") (pin "55") (pinfunction "PB3_55") (pintype "passive"))
    )
    (net (code "80") (name "unconnected-(U1-PB5-Pad57)") (class "Default")
      (node (ref "U1") (pin "57") (pinfunction "PB5_57") (pintype "passive"))
    )
    (net (code "81") (name "unconnected-(U1-PB8-Pad61)") (class "Default")
      (node (ref "U1") (pin "61") (pinfunction "PB8_61") (pintype "passive"))
    )
    (net (code "82") (name "unconnected-(U1-PB9-Pad62)") (class "Default")
      (node (ref "U1") (pin "62") (pinfunction "PB9_62") (pintype "passive"))
    )
    (net (code "83") (name "unconnected-(U1-PC0-Pad8)") (class "Default")
      (node (ref "U1") (pin "8") (pinfunction "PC0_8") (pintype "passive"))
    )
    (net (code "84") (name "unconnected-(U1-PC3-Pad11)") (class "Default")
      (node (ref "U1") (pin "11") (pinfunction "PC3_11") (pintype "passive"))
    )
    (net (code "85") (name "unconnected-(U1-PC13-Pad2)") (class "Default")
      (node (ref "U1") (pin "2") (pinfunction "PC13_2") (pintype "passive"))
    )
    (net (code "86") (name "unconnected-(U3-TAB-Pad4)") (class "Default")
      (node (ref "U3") (pin "4") (pinfunction "TAB_4") (pintype "passive+no_connect"))
    )
    (net (code "87") (name "unconnected-(U4-EXP-Pad25)") (class "Default")
      (node (ref "U4") (pin "25") (pinfunction "EXP_25") (pintype "passive"))
    )
    (net (code "88") (name "unconnected-(U4-NC-Pad2)") (class "Default")
      (node (ref "U4") (pin "2") (pinfunction "NC_2") (pintype "passive"))
    )
    (net (code "89") (name "unconnected-(U4-NC-Pad3)") (class "Default")
      (node (ref "U4") (pin "3") (pinfunction "NC_3") (pintype "passive"))
    )
    (net (code "90") (name "unconnected-(U4-NC-Pad4)") (class "Default")
      (node (ref "U4") (pin "4") (pinfunction "NC_4") (pintype "passive"))
    )
    (net (code "91") (name "unconnected-(U4-NC-Pad5)") (class "Default")
      (node (ref "U4") (pin "5") (pinfunction "NC_5") (pintype "passive"))
    )
    (net (code "92") (name "unconnected-(U4-NC-Pad6)") (class "Default")
      (node (ref "U4") (pin "6") (pinfunction "NC_6") (pintype "passive"))
    )
    (net (code "93") (name "unconnected-(U4-NC-Pad14)") (class "Default")
      (node (ref "U4") (pin "14") (pinfunction "NC_14") (pintype "passive"))
    )
    (net (code "94") (name "unconnected-(U4-NC-Pad15)") (class "Default")
      (node (ref "U4") (pin "15") (pinfunction "NC_15") (pintype "passive"))
    )
    (net (code "95") (name "unconnected-(U4-NC-Pad16)") (class "Default")
      (node (ref "U4") (pin "16") (pinfunction "NC_16") (pintype "passive"))
    )
    (net (code "96") (name "unconnected-(U4-NC-Pad17)") (class "Default")
      (node (ref "U4") (pin "17") (pinfunction "NC_17") (pintype "passive"))
    )
    (net (code "97") (name "unconnected-(U4-RESV-Pad19)") (class "Default")
      (node (ref "U4") (pin "19") (pinfunction "RESV_19") (pintype "passive"))
    )
    (net (code "98") (name "unconnected-(U5-DB0-Pad16)") (class "Default")
      (node (ref "U5") (pin "16") (pinfunction "DB0_16") (pintype "passive"))
    )
    (net (code "99") (name "unconnected-(U5-DB1-Pad17)") (class "Default")
      (node (ref "U5") (pin "17") (pinfunction "DB1_17") (pintype "passive"))
    )
    (net (code "100") (name "unconnected-(U5-DB2-Pad18)") (class "Default")
      (node (ref "U5") (pin "18") (pinfunction "DB2_18") (pintype "passive"))
    )
    (net (code "101") (name "unconnected-(U5-DB3-Pad19)") (class "Default")
      (node (ref "U5") (pin "19") (pinfunction "DB3_19") (pintype "passive"))
    )
    (net (code "102") (name "unconnected-(U5-DB4-Pad20)") (class "Default")
      (node (ref "U5") (pin "20") (pinfunction "DB4_20") (pintype "passive"))
    )
    (net (code "103") (name "unconnected-(U5-DB5-Pad21)") (class "Default")
      (node (ref "U5") (pin "21") (pinfunction "DB5_21") (pintype "passive"))
    )
    (net (code "104") (name "unconnected-(U5-DB6-Pad22)") (class "Default")
      (node (ref "U5") (pin "22") (pinfunction "DB6_22") (pintype "passive"))
    )
    (net (code "105") (name "unconnected-(U5-DB9-Pad27)") (class "Default")
      (node (ref "U5") (pin "27") (pinfunction "DB9_27") (pintype "passive"))
    )
    (net (code "106") (name "unconnected-(U5-DB10-Pad28)") (class "Default")
      (node (ref "U5") (pin "28") (pinfunction "DB10_28") (pintype "passive"))
    )
    (net (code "107") (name "unconnected-(U5-DB11-Pad29)") (class "Default")
      (node (ref "U5") (pin "29") (pinfunction "DB11_29") (pintype "passive"))
    )
    (net (code "108") (name "unconnected-(U5-DB12-Pad30)") (class "Default")
      (node (ref "U5") (pin "30") (pinfunction "DB12_30") (pintype "passive"))
    )
    (net (code "109") (name "unconnected-(U5-DB13-Pad31)") (class "Default")
      (node (ref "U5") (pin "31") (pinfunction "DB13_31") (pintype "passive"))
    )
    (net (code "110") (name "unconnected-(U5-DB14{slash}HBEN-Pad32)") (class "Default")
      (node (ref "U5") (pin "32") (pinfunction "DB14/HBEN_32") (pintype "passive"))
    )
    (net (code "111") (name "unconnected-(U6-TRIM-Pad5)") (class "Default")
      (node (ref "U6") (pin "5") (pinfunction "TRIM_5") (pintype "passive"))
    )
    (net (code "112") (name "unconnected-(XS1-D+-Pad3)") (class "Default")
      (node (ref "XS1") (pin "3") (pinfunction "D+_3") (pintype "passive"))
    )
    (net (code "113") (name "unconnected-(XS1-D--Pad2)") (class "Default")
      (node (ref "XS1") (pin "2") (pinfunction "D-_2") (pintype "passive"))
    )
    (net (code "114") (name "unconnected-(XS1-ID-Pad4)") (class "Default")
      (node (ref "XS1") (pin "4") (pinfunction "ID_4") (pintype "passive"))
    )
  )
)
